# napajanje.net
KiCad netlist of a schematic drawn in Altium Designer
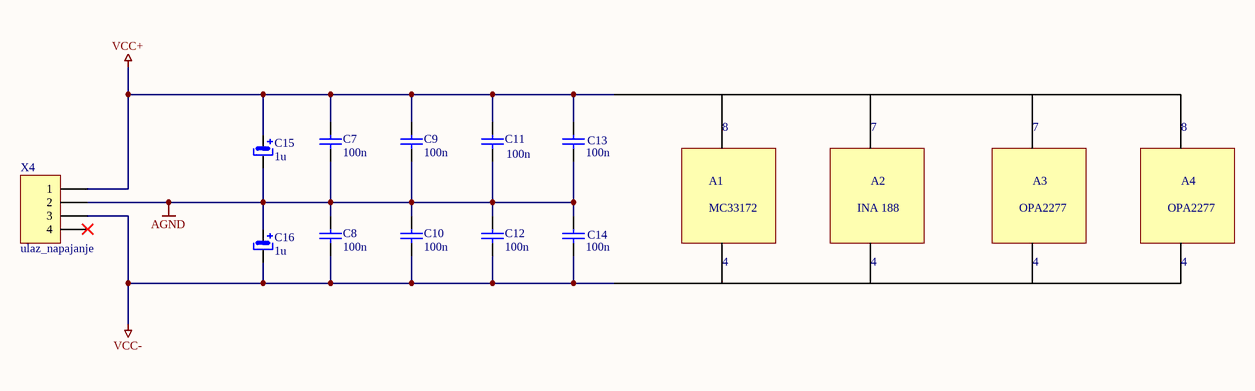
[diagram p0: napajanje.SchDoc]

(export (version "E")
  (design (tool "Eeschema 10.0.6"))
  (components
    (comp (ref "C7")
      (value "100n")
      (footprint "C0805")
      (description "Capacitor")
      (fields (field (name "PUBLISHER") "Altium Limited"))
      (libsource (lib "Miscellaneous Devices") (part "Cap"))
    )
    (comp (ref "C8")
      (value "100n")
      (footprint "C0805")
      (description "Capacitor")
      (fields (field (name "PUBLISHER") "Altium Limited"))
      (libsource (lib "Miscellaneous Devices") (part "Cap"))
    )
    (comp (ref "C9")
      (value "100n")
      (footprint "C0805")
      (description "Capacitor")
      (fields (field (name "PUBLISHER") "Altium Limited"))
      (libsource (lib "Miscellaneous Devices") (part "Cap"))
    )
    (comp (ref "C10")
      (value "100n")
      (footprint "C0805")
      (description "Capacitor")
      (fields (field (name "PUBLISHER") "Altium Limited"))
      (libsource (lib "Miscellaneous Devices") (part "Cap"))
    )
    (comp (ref "C11")
      (value "100n")
      (footprint "C0805")
      (description "Capacitor")
      (fields (field (name "PUBLISHER") "Altium Limited"))
      (libsource (lib "Miscellaneous Devices") (part "Cap"))
    )
    (comp (ref "C12")
      (value "100n")
      (footprint "C0805")
      (description "Capacitor")
      (fields (field (name "PUBLISHER") "Altium Limited"))
      (libsource (lib "Miscellaneous Devices") (part "Cap"))
    )
    (comp (ref "C13")
      (value "100n")
      (footprint "C0805")
      (description "Capacitor")
      (fields (field (name "PUBLISHER") "Altium Limited"))
      (libsource (lib "Miscellaneous Devices") (part "Cap"))
    )
    (comp (ref "C14")
      (value "100n")
      (footprint "C0805")
      (description "Capacitor")
      (fields (field (name "PUBLISHER") "Altium Limited"))
      (libsource (lib "Miscellaneous Devices") (part "Cap"))
    )
    (comp (ref "C15")
      (value "1u")
      (footprint "6-0805_M")
      (libsource (lib "altium-import") (part "root_0_elko_"))
    )
    (comp (ref "C16")
      (value "1u")
      (footprint "6-0805_M")
      (libsource (lib "altium-import") (part "root_0_elko_"))
    )
    (comp (ref "X4")
      (value "ulaz_napajanje")
      (footprint "HDR1X4")
      (description "Header, 4-Pin, Right Angle")
      (fields (field (name "PUBLISHER") "Altium Limited"))
      (libsource (lib "Miscellaneous Connectors") (part "Header 4H"))
    )
  )
  (nets
    (net (code "1") (name "AGND") (class "Default")
      (node (ref "C10") (pin "2") (pinfunction "2_2") (pintype "passive"))
      (node (ref "C11") (pin "1") (pinfunction "1_1") (pintype "passive"))
      (node (ref "C12") (pin "2") (pinfunction "2_2") (pintype "passive"))
      (node (ref "C13") (pin "1") (pinfunction "1_1") (pintype "passive"))
      (node (ref "C14") (pin "2") (pinfunction "2_2") (pintype "passive"))
      (node (ref "C15") (pin "2") (pinfunction "2_2") (pintype "passive"))
      (node (ref "C16") (pin "1") (pinfunction "1_1") (pintype "passive"))
      (node (ref "C7") (pin "1") (pinfunction "1_1") (pintype "passive"))
      (node (ref "C8") (pin "2") (pinfunction "2_2") (pintype "passive"))
      (node (ref "C9") (pin "1") (pinfunction "1_1") (pintype "passive"))
      (node (ref "X4") (pin "2") (pinfunction "2_2") (pintype "passive"))
    )
    (net (code "2") (name "VCC+") (class "Default")
      (node (ref "C11") (pin "2") (pinfunction "2_2") (pintype "passive"))
      (node (ref "C13") (pin "2") (pinfunction "2_2") (pintype "passive"))
      (node (ref "C15") (pin "1") (pinfunction "1_1") (pintype "passive"))
      (node (ref "C7") (pin "2") (pinfunction "2_2") (pintype "passive"))
      (node (ref "C9") (pin "2") (pinfunction "2_2") (pintype "passive"))
      (node (ref "X4") (pin "1") (pinfunction "1_1") (pintype "passive"))
    )
    (net (code "3") (name "VCC-") (class "Default")
      (node (ref "C10") (pin "1") (pinfunction "1_1") (pintype "passive"))
      (node (ref "C12") (pin "1") (pinfunction "1_1") (pintype "passive"))
      (node (ref "C14") (pin "1") (pinfunction "1_1") (pintype "passive"))
      (node (ref "C16") (pin "2") (pinfunction "2_2") (pintype "passive"))
      (node (ref "C8") (pin "1") (pinfunction "1_1") (pintype "passive"))
      (node (ref "X4") (pin "3") (pinfunction "3_3") (pintype "passive"))
    )
    (net (code "4") (name "unconnected-(X4-Pad4)") (class "Default")
      (node (ref "X4") (pin "4") (pinfunction "4_4") (pintype "passive+no_connect"))
    )
  )
)
